# 230V2LED.net
KiCad netlist of a schematic drawn in EAGLE
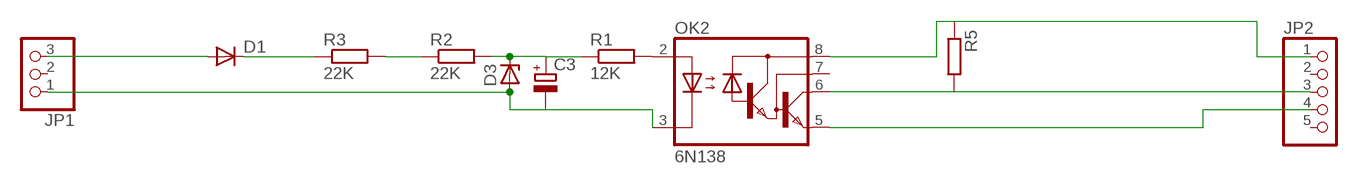
[diagram p0: schematic, sheet 1]

(export (version "E")
  (design (tool "Eeschema 10.0.6"))
  (components
    (comp (ref "C3")
      (value "CPOL-EUE2,5-6E")
      (footprint "eagle-import:E2,5-6E")
      (libsource (lib "eagle-import") (part "CPOL-EUE2,5-6E"))
    )
    (comp (ref "D1")
      (value "DIODE-D-2.5")
      (footprint "eagle-import:D-2.5")
      (libsource (lib "eagle-import") (part "DIODE-D-2.5"))
    )
    (comp (ref "D3")
      (value "ZENER-DIODEZD-2.5")
      (footprint "eagle-import:ZDIO-2.5")
      (libsource (lib "eagle-import") (part "ZENER-DIODEZD-2.5"))
    )
    (comp (ref "JP1")
      (value "PINHD-1X3")
      (footprint "eagle-import:1X03")
      (libsource (lib "eagle-import") (part "PINHD-1X3"))
    )
    (comp (ref "JP2")
      (value "PINHD-1X5")
      (footprint "eagle-import:1X05")
      (libsource (lib "eagle-import") (part "PINHD-1X5"))
    )
    (comp (ref "OK2")
      (value "6N138")
      (footprint "eagle-import:DIL08")
      (fields (field (name "MF") "VISHAY/TELEFUNKEN"))
      (libsource (lib "eagle-import") (part "6N138"))
    )
    (comp (ref "R1")
      (value "12K")
      (footprint "eagle-import:0207_2V")
      (libsource (lib "eagle-import") (part "R-EU_0207/2V"))
    )
    (comp (ref "R2")
      (value "22K")
      (footprint "eagle-import:0207_2V")
      (libsource (lib "eagle-import") (part "R-EU_0207/2V"))
    )
    (comp (ref "R3")
      (value "22K")
      (footprint "eagle-import:0207_2V")
      (libsource (lib "eagle-import") (part "R-EU_0207/2V"))
    )
    (comp (ref "R5")
      (value "R-EU_0207/2V")
      (footprint "eagle-import:0207_2V")
      (libsource (lib "eagle-import") (part "R-EU_0207/2V"))
    )
  )
  (nets
    (net (code "1") (name "Net-(C3-Pad+)") (class "Default")
      (node (ref "C3") (pin "+") (pinfunction "+_+") (pintype "passive"))
      (node (ref "D3") (pin "C") (pinfunction "C_C") (pintype "passive"))
      (node (ref "R1") (pin "1") (pinfunction "1_1") (pintype "passive"))
      (node (ref "R2") (pin "2") (pinfunction "2_2") (pintype "passive"))
    )
    (net (code "2") (name "Net-(D1-PadA)") (class "Default")
      (node (ref "D1") (pin "A") (pinfunction "A_A") (pintype "passive"))
      (node (ref "JP1") (pin "3") (pinfunction "3_3") (pintype "passive"))
    )
    (net (code "3") (name "Net-(D1-PadC)") (class "Default")
      (node (ref "D1") (pin "C") (pinfunction "C_C") (pintype "passive"))
      (node (ref "R3") (pin "1") (pinfunction "1_1") (pintype "passive"))
    )
    (net (code "4") (name "Net-(OK2-A)") (class "Default")
      (node (ref "OK2") (pin "2") (pinfunction "A_2") (pintype "passive"))
      (node (ref "R1") (pin "2") (pinfunction "2_2") (pintype "passive"))
    )
    (net (code "5") (name "Net-(OK2-C)") (class "Default")
      (node (ref "C3") (pin "-") (pinfunction "-_-") (pintype "passive"))
      (node (ref "D3") (pin "A") (pinfunction "A_A") (pintype "passive"))
      (node (ref "JP1") (pin "1") (pinfunction "1_1") (pintype "passive"))
      (node (ref "OK2") (pin "3") (pinfunction "C_3") (pintype "passive"))
    )
    (net (code "6") (name "Net-(OK2-GND)") (class "Default")
      (node (ref "JP2") (pin "4") (pinfunction "4_4") (pintype "passive"))
      (node (ref "OK2") (pin "5") (pinfunction "GND_5") (pintype "passive"))
    )
    (net (code "7") (name "Net-(OK2-VCC)") (class "Default")
      (node (ref "JP2") (pin "1") (pinfunction "1_1") (pintype "passive"))
      (node (ref "OK2") (pin "8") (pinfunction "VCC_8") (pintype "passive"))
      (node (ref "R5") (pin "1") (pinfunction "1_1") (pintype "passive"))
    )
    (net (code "8") (name "Net-(OK2-VO)") (class "Default")
      (node (ref "JP2") (pin "3") (pinfunction "3_3") (pintype "passive"))
      (node (ref "OK2") (pin "6") (pinfunction "VO_6") (pintype "passive"))
      (node (ref "R5") (pin "2") (pinfunction "2_2") (pintype "passive"))
    )
    (net (code "9") (name "Net-(R2-Pad1)") (class "Default")
      (node (ref "R2") (pin "1") (pinfunction "1_1") (pintype "passive"))
      (node (ref "R3") (pin "2") (pinfunction "2_2") (pintype "passive"))
    )
    (net (code "10") (name "unconnected-(JP1-Pad2)") (class "Default")
      (node (ref "JP1") (pin "2") (pinfunction "2_2") (pintype "passive"))
    )
    (net (code "11") (name "unconnected-(JP2-Pad2)") (class "Default")
      (node (ref "JP2") (pin "2") (pinfunction "2_2") (pintype "passive"))
    )
    (net (code "12") (name "unconnected-(JP2-Pad5)") (class "Default")
      (node (ref "JP2") (pin "5") (pinfunction "5_5") (pintype "passive"))
    )
    (net (code "13") (name "unconnected-(OK2-VB-Pad7)") (class "Default")
      (node (ref "OK2") (pin "7") (pinfunction "VB_7") (pintype "passive"))
    )
  )
)
